# Mirror_TurnSignal_-_Connectors_and_Power.net
KiCad netlist of a schematic drawn in Altium Designer
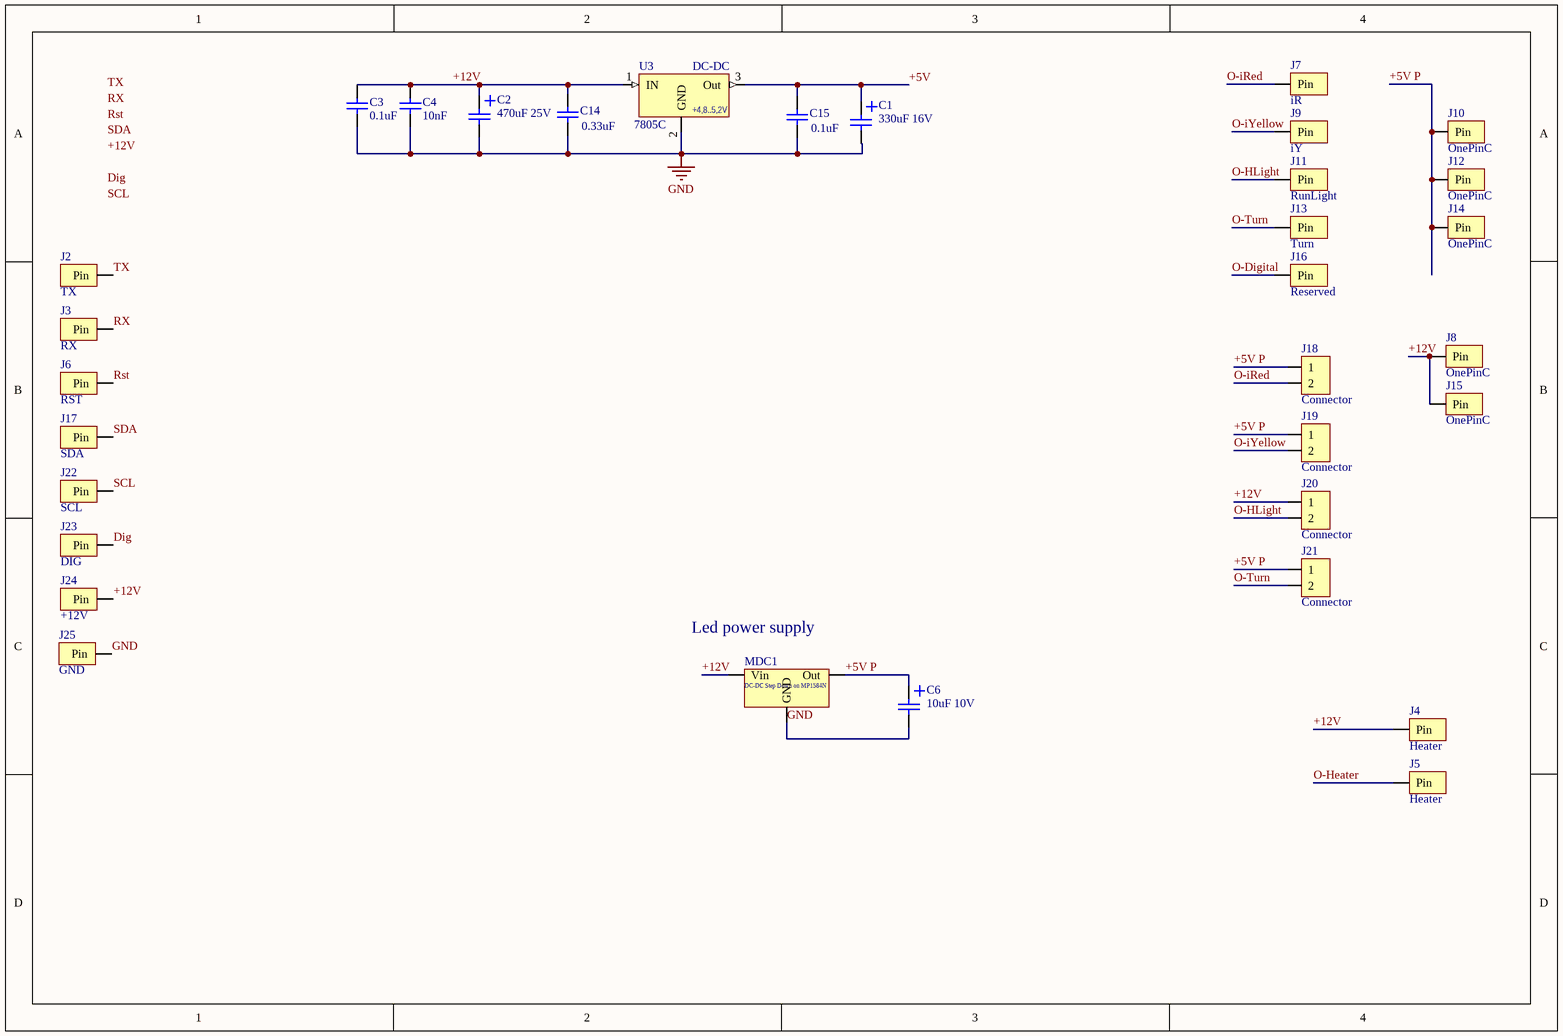
[diagram p0: Mirror TurnSignal - Connectors and Power supply.SchDoc]

(export (version "E")
  (design (tool "Eeschema 10.0.6"))
  (components
    (comp (ref "C1")
      (value "330uF 16V")
      (footprint "Capacitor:Cap E p2.54mm D4xH8 (2p)")
      (description "Capacitor")
      (libsource (lib "Capacitor") (part "Cap Elecrolitic"))
    )
    (comp (ref "C2")
      (value "470uF 25V")
      (footprint "Capacitor:Cap E p2.54mm D4xH8 (2p)")
      (description "Capacitor")
      (libsource (lib "Capacitor") (part "Cap Elecrolitic"))
    )
    (comp (ref "C3")
      (value "0.1uF")
      (footprint "Capacitor:SMD 0805 (2012)")
      (description "Capacitor")
      (libsource (lib "Capacitor") (part "Cap SMD 0402-1812"))
    )
    (comp (ref "C4")
      (value "10nF")
      (footprint "Capacitor:SMD 0805 (2012)")
      (description "Capacitor")
      (libsource (lib "Capacitor") (part "Cap SMD 0402-1812"))
    )
    (comp (ref "C6")
      (value "10uF 10V")
      (footprint "Capacitor:Cap E p1.5mm D4xH8 (2p)")
      (description "Capacitor")
      (libsource (lib "Capacitor") (part "Cap Elecrolitic"))
    )
    (comp (ref "C14")
      (value "0.33uF")
      (footprint "Capacitor:SMD 1206 (3216)")
      (description "Capacitor")
      (libsource (lib "Capacitor") (part "Cap SMD 0402-1812"))
    )
    (comp (ref "C15")
      (value "0.1uF")
      (footprint "Capacitor:SMD 1206 (3216)")
      (description "Capacitor")
      (libsource (lib "Capacitor") (part "Cap SMD 0402-1812"))
    )
    (comp (ref "J2")
      (value "TX")
      (footprint "Connector:OnePin 0.7x2")
      (description "Only pad")
      (libsource (lib "") (part "OnePin Connector_1"))
    )
    (comp (ref "J3")
      (value "RX")
      (footprint "Connector:OnePin 0.7x2")
      (description "Only pad")
      (libsource (lib "") (part "OnePin Connector_1"))
    )
    (comp (ref "J4")
      (value "Heater")
      (footprint "Connector:OnePin 3x10mm Hole 0.7x8")
      (description "Only pad")
      (libsource (lib "Connector") (part "OnePin Connector"))
    )
    (comp (ref "J5")
      (value "Heater")
      (footprint "Connector:OnePin 3x10mm Hole 0.7x8")
      (description "Only pad")
      (libsource (lib "Connector") (part "OnePin Connector"))
    )
    (comp (ref "J6")
      (value "RST")
      (footprint "Connector:OnePin 0.7x2")
      (description "Only pad")
      (libsource (lib "") (part "OnePin Connector_1"))
    )
    (comp (ref "J7")
      (value "iR")
      (footprint "Connector:OnePin 1.2x3")
      (description "Only pad")
      (libsource (lib "Connector") (part "OnePin Connector"))
    )
    (comp (ref "J8")
      (value "OnePinC")
      (footprint "Connector:OnePin 1.2x3")
      (description "Only pad")
      (libsource (lib "Connector") (part "OnePin Connector"))
    )
    (comp (ref "J9")
      (value "iY")
      (footprint "Connector:OnePin 1.2x3")
      (description "Only pad")
      (libsource (lib "Connector") (part "OnePin Connector"))
    )
    (comp (ref "J10")
      (value "OnePinC")
      (footprint "Connector:OnePin 1.2x3")
      (description "Only pad")
      (libsource (lib "Connector") (part "OnePin Connector"))
    )
    (comp (ref "J11")
      (value "RunLight")
      (footprint "Connector:OnePin 1.2x3")
      (description "Only pad")
      (libsource (lib "Connector") (part "OnePin Connector"))
    )
    (comp (ref "J12")
      (value "OnePinC")
      (footprint "Connector:OnePin 1.2x3")
      (description "Only pad")
      (libsource (lib "Connector") (part "OnePin Connector"))
    )
    (comp (ref "J13")
      (value "Turn")
      (footprint "Connector:OnePin 1.2x3")
      (description "Only pad")
      (libsource (lib "Connector") (part "OnePin Connector"))
    )
    (comp (ref "J14")
      (value "OnePinC")
      (footprint "Connector:OnePin 1.2x3")
      (description "Only pad")
      (libsource (lib "Connector") (part "OnePin Connector"))
    )
    (comp (ref "J15")
      (value "OnePinC")
      (footprint "Connector:OnePin 1.2x3")
      (description "Only pad")
      (libsource (lib "Connector") (part "OnePin Connector"))
    )
    (comp (ref "J16")
      (value "Reserved")
      (footprint "Connector:OnePin 1.2x3")
      (description "Only pad")
      (libsource (lib "Connector") (part "OnePin Connector"))
    )
    (comp (ref "J17")
      (value "SDA")
      (footprint "Connector:OnePin 0.7x2")
      (description "Only pad")
      (libsource (lib "") (part "OnePin Connector_1"))
    )
    (comp (ref "J18")
      (value "Connector")
      (footprint "Connector:CWF-2")
      (description "CWF series")
      (libsource (lib "Connector") (part "CWF-2 (R)"))
    )
    (comp (ref "J19")
      (value "Connector")
      (footprint "Connector:CWF-2")
      (description "CWF series")
      (libsource (lib "Connector") (part "CWF-2 (R)"))
    )
    (comp (ref "J20")
      (value "Connector")
      (footprint "Connector:CWF-2")
      (description "CWF series")
      (libsource (lib "Connector") (part "CWF-2 (R)"))
    )
    (comp (ref "J21")
      (value "Connector")
      (footprint "Connector:CWF-2")
      (description "CWF series")
      (libsource (lib "Connector") (part "CWF-2 (R)"))
    )
    (comp (ref "J22")
      (value "SCL")
      (footprint "Connector:OnePin 0.7x2")
      (description "Only pad")
      (libsource (lib "") (part "OnePin Connector_1"))
    )
    (comp (ref "J23")
      (value "DIG")
      (footprint "Connector:OnePin 0.7x2")
      (description "Only pad")
      (libsource (lib "") (part "OnePin Connector_1"))
    )
    (comp (ref "J24")
      (value "+12V")
      (footprint "Connector:OnePin 0.7x2")
      (description "Only pad")
      (libsource (lib "") (part "OnePin Connector_1"))
    )
    (comp (ref "J25")
      (value "GND")
      (footprint "Connector:OnePin 0.7x2")
      (description "Only pad")
      (libsource (lib "") (part "OnePin Connector_1"))
    )
    (comp (ref "MDC1")
      (value "DC-DC")
      (footprint "Modules:DC-DC_MP1584N - spec1 (less pins)")
      (description "DC-DC StepDown")
      (libsource (lib "Modules") (part "DC-DC MP1584N"))
    )
    (comp (ref "U3")
      (value "7805C")
      (footprint "GeneralCases:D-PAK")
      (description "Voltage Regulator")
      (fields (field (name "MANUFACTURER") "Интеграл") (field (name "V OUT") "+4,8..5,2V"))
      (libsource (lib "PowerAdjusment") (part "7805C"))
    )
  )
  (nets
    (net (code "1") (name "/+5V") (class "Default")
      (node (ref "C1") (pin "1") (pinfunction "1_1") (pintype "passive"))
      (node (ref "C15") (pin "1") (pinfunction "1_1") (pintype "passive"))
      (node (ref "U3") (pin "3") (pinfunction "Out_3") (pintype "output"))
    )
    (net (code "2") (name "/+5V P") (class "Default")
      (node (ref "C6") (pin "1") (pinfunction "1_1") (pintype "passive"))
      (node (ref "J10") (pin "1") (pinfunction "Pin_1") (pintype "passive"))
      (node (ref "J12") (pin "1") (pinfunction "Pin_1") (pintype "passive"))
      (node (ref "J14") (pin "1") (pinfunction "Pin_1") (pintype "passive"))
      (node (ref "J18") (pin "1") (pinfunction "1_1") (pintype "passive"))
      (node (ref "J19") (pin "1") (pinfunction "1_1") (pintype "passive"))
      (node (ref "J21") (pin "1") (pinfunction "1_1") (pintype "passive"))
      (node (ref "MDC1") (pin "OUT") (pinfunction "Out_OUT") (pintype "passive"))
    )
    (net (code "3") (name "/+12V") (class "Default")
      (node (ref "C14") (pin "1") (pinfunction "1_1") (pintype "passive"))
      (node (ref "C2") (pin "1") (pinfunction "1_1") (pintype "passive"))
      (node (ref "C3") (pin "1") (pinfunction "1_1") (pintype "passive"))
      (node (ref "C4") (pin "1") (pinfunction "1_1") (pintype "passive"))
      (node (ref "J15") (pin "1") (pinfunction "Pin_1") (pintype "passive"))
      (node (ref "J20") (pin "1") (pinfunction "1_1") (pintype "passive"))
      (node (ref "J24") (pin "1") (pinfunction "Pin_1") (pintype "passive"))
      (node (ref "J4") (pin "1") (pinfunction "Pin_1") (pintype "passive"))
      (node (ref "J8") (pin "1") (pinfunction "Pin_1") (pintype "passive"))
      (node (ref "MDC1") (pin "IN") (pinfunction "Vin_IN") (pintype "passive"))
      (node (ref "U3") (pin "1") (pinfunction "IN_1") (pintype "input"))
    )
    (net (code "4") (name "/Dig") (class "Default")
      (node (ref "J23") (pin "1") (pinfunction "Pin_1") (pintype "passive"))
    )
    (net (code "5") (name "/O-Digital") (class "Default")
      (node (ref "J16") (pin "1") (pinfunction "Pin_1") (pintype "passive"))
    )
    (net (code "6") (name "/O-HLight") (class "Default")
      (node (ref "J11") (pin "1") (pinfunction "Pin_1") (pintype "passive"))
      (node (ref "J20") (pin "2") (pinfunction "2_2") (pintype "passive"))
    )
    (net (code "7") (name "/O-Heater") (class "Default")
      (node (ref "J5") (pin "1") (pinfunction "Pin_1") (pintype "passive"))
    )
    (net (code "8") (name "/O-Turn") (class "Default")
      (node (ref "J13") (pin "1") (pinfunction "Pin_1") (pintype "passive"))
      (node (ref "J21") (pin "2") (pinfunction "2_2") (pintype "passive"))
    )
    (net (code "9") (name "/O-iRed") (class "Default")
      (node (ref "J18") (pin "2") (pinfunction "2_2") (pintype "passive"))
      (node (ref "J7") (pin "1") (pinfunction "Pin_1") (pintype "passive"))
    )
    (net (code "10") (name "/O-iYellow") (class "Default")
      (node (ref "J19") (pin "2") (pinfunction "2_2") (pintype "passive"))
      (node (ref "J9") (pin "1") (pinfunction "Pin_1") (pintype "passive"))
    )
    (net (code "11") (name "/RX") (class "Default")
      (node (ref "J3") (pin "1") (pinfunction "Pin_1") (pintype "passive"))
    )
    (net (code "12") (name "/Rst") (class "Default")
      (node (ref "J6") (pin "1") (pinfunction "Pin_1") (pintype "passive"))
    )
    (net (code "13") (name "/SCL") (class "Default")
      (node (ref "J22") (pin "1") (pinfunction "Pin_1") (pintype "passive"))
    )
    (net (code "14") (name "/SDA") (class "Default")
      (node (ref "J17") (pin "1") (pinfunction "Pin_1") (pintype "passive"))
    )
    (net (code "15") (name "/TX") (class "Default")
      (node (ref "J2") (pin "1") (pinfunction "Pin_1") (pintype "passive"))
    )
    (net (code "16") (name "GND") (class "Default")
      (node (ref "C1") (pin "2") (pinfunction "2_2") (pintype "passive"))
      (node (ref "C14") (pin "2") (pinfunction "2_2") (pintype "passive"))
      (node (ref "C15") (pin "2") (pinfunction "2_2") (pintype "passive"))
      (node (ref "C2") (pin "2") (pinfunction "2_2") (pintype "passive"))
      (node (ref "C3") (pin "2") (pinfunction "2_2") (pintype "passive"))
      (node (ref "C4") (pin "2") (pinfunction "2_2") (pintype "passive"))
      (node (ref "C6") (pin "2") (pinfunction "2_2") (pintype "passive"))
      (node (ref "J25") (pin "1") (pinfunction "Pin_1") (pintype "passive"))
      (node (ref "MDC1") (pin "GND") (pinfunction "GND_GND") (pintype "passive"))
      (node (ref "U3") (pin "2") (pinfunction "GND_2") (pintype "passive"))
    )
  )
)
